# PCB_eagle_project.net
KiCad netlist of a schematic drawn in EAGLE
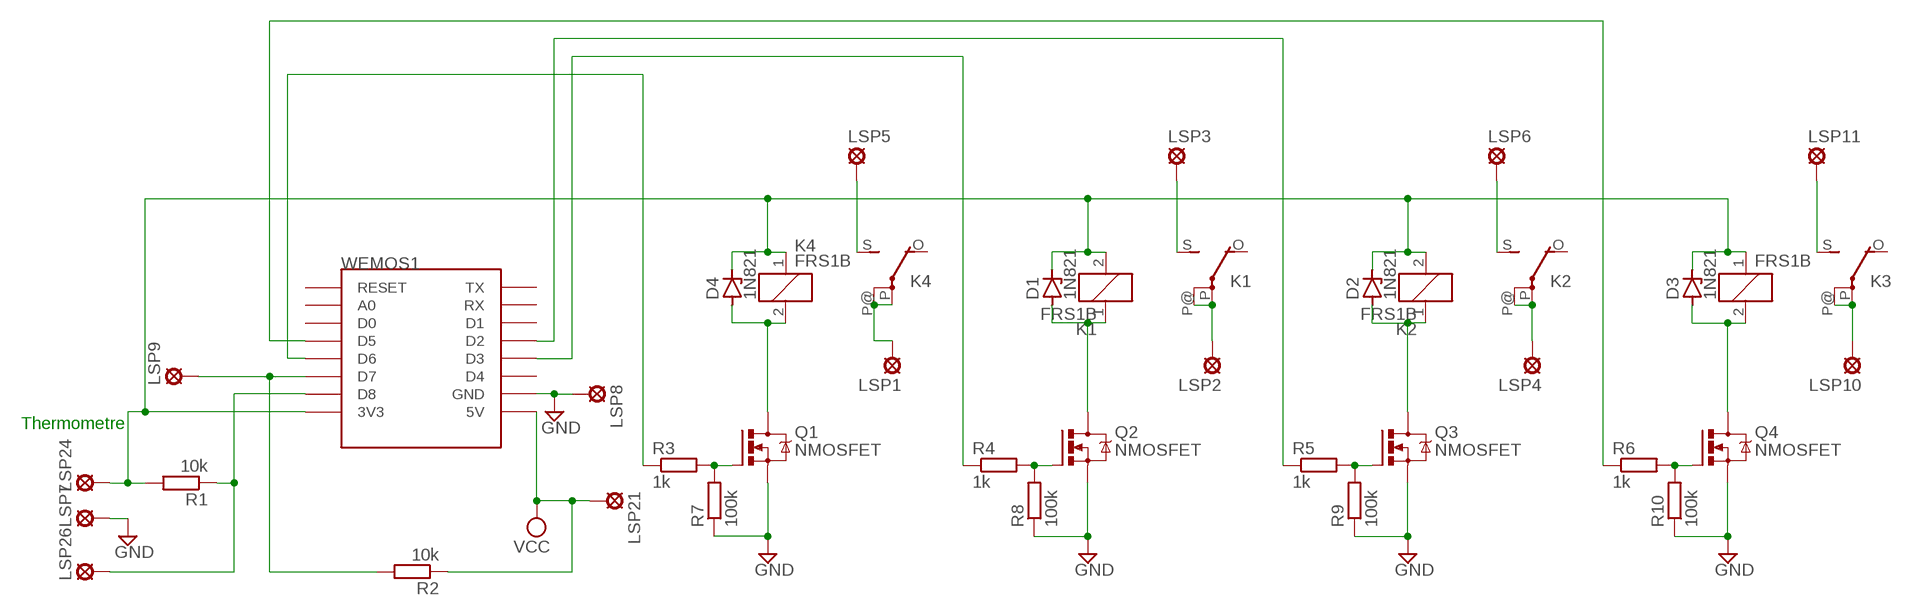
[diagram p0: schematic, sheet 1]

(export (version "E")
  (design (tool "Eeschema 10.0.6"))
  (components
    (comp (ref "D1")
      (value "1N821")
      (footprint "eagle-import:DO35Z10")
      (libsource (lib "eagle-import") (part "1N821"))
    )
    (comp (ref "D2")
      (value "1N821")
      (footprint "eagle-import:DO35Z10")
      (libsource (lib "eagle-import") (part "1N821"))
    )
    (comp (ref "D3")
      (value "1N821")
      (footprint "eagle-import:DO35Z10")
      (libsource (lib "eagle-import") (part "1N821"))
    )
    (comp (ref "D4")
      (value "1N821")
      (footprint "eagle-import:DO35Z10")
      (libsource (lib "eagle-import") (part "1N821"))
    )
    (comp (ref "K1")
      (value "FRS1B")
      (footprint "eagle-import:FRS1B")
      (libsource (lib "eagle-import") (part "FRS1B"))
    )
    (comp (ref "K2")
      (value "FRS1B")
      (footprint "eagle-import:FRS1B")
      (libsource (lib "eagle-import") (part "FRS1B"))
    )
    (comp (ref "K3")
      (value "FRS1B")
      (footprint "eagle-import:FRS1B")
      (libsource (lib "eagle-import") (part "FRS1B"))
    )
    (comp (ref "K4")
      (value "FRS1B")
      (footprint "eagle-import:FRS1B")
      (libsource (lib "eagle-import") (part "FRS1B"))
    )
    (comp (ref "LSP1")
      (value "MCS10B")
      (footprint "eagle-import:MCS10B")
      (libsource (lib "eagle-import") (part "MCS10B"))
    )
    (comp (ref "LSP2")
      (value "MCS10B")
      (footprint "eagle-import:MCS10B")
      (libsource (lib "eagle-import") (part "MCS10B"))
    )
    (comp (ref "LSP3")
      (value "MCS10B")
      (footprint "eagle-import:MCS10B")
      (libsource (lib "eagle-import") (part "MCS10B"))
    )
    (comp (ref "LSP4")
      (value "MCS10B")
      (footprint "eagle-import:MCS10B")
      (libsource (lib "eagle-import") (part "MCS10B"))
    )
    (comp (ref "LSP5")
      (value "MCS10B")
      (footprint "eagle-import:MCS10B")
      (libsource (lib "eagle-import") (part "MCS10B"))
    )
    (comp (ref "LSP6")
      (value "MCS10B")
      (footprint "eagle-import:MCS10B")
      (libsource (lib "eagle-import") (part "MCS10B"))
    )
    (comp (ref "LSP7")
      (value "MCS10B")
      (footprint "eagle-import:MCS10B")
      (libsource (lib "eagle-import") (part "MCS10B"))
    )
    (comp (ref "LSP8")
      (value "MCS10B")
      (footprint "eagle-import:MCS10B")
      (libsource (lib "eagle-import") (part "MCS10B"))
    )
    (comp (ref "LSP9")
      (value "MCS10B")
      (footprint "eagle-import:MCS10B")
      (libsource (lib "eagle-import") (part "MCS10B"))
    )
    (comp (ref "LSP10")
      (value "MCS10B")
      (footprint "eagle-import:MCS10B")
      (libsource (lib "eagle-import") (part "MCS10B"))
    )
    (comp (ref "LSP11")
      (value "MCS10B")
      (footprint "eagle-import:MCS10B")
      (libsource (lib "eagle-import") (part "MCS10B"))
    )
    (comp (ref "LSP21")
      (value "MCS10B")
      (footprint "eagle-import:MCS10B")
      (libsource (lib "eagle-import") (part "MCS10B"))
    )
    (comp (ref "LSP24")
      (value "MCS10B")
      (footprint "eagle-import:MCS10B")
      (libsource (lib "eagle-import") (part "MCS10B"))
    )
    (comp (ref "LSP26")
      (value "MCS10B")
      (footprint "eagle-import:MCS10B")
      (libsource (lib "eagle-import") (part "MCS10B"))
    )
    (comp (ref "Q1")
      (value "NMOSFET")
      (footprint "eagle-import:SOT23")
      (libsource (lib "eagle-import") (part "NMOSFETSOT23-GSD"))
    )
    (comp (ref "Q2")
      (value "NMOSFET")
      (footprint "eagle-import:SOT23")
      (libsource (lib "eagle-import") (part "NMOSFETSOT23-GSD"))
    )
    (comp (ref "Q3")
      (value "NMOSFET")
      (footprint "eagle-import:SOT23")
      (libsource (lib "eagle-import") (part "NMOSFETSOT23-GSD"))
    )
    (comp (ref "Q4")
      (value "NMOSFET")
      (footprint "eagle-import:SOT23")
      (libsource (lib "eagle-import") (part "NMOSFETSOT23-GSD"))
    )
    (comp (ref "R1")
      (value "10k")
      (footprint "eagle-import:0207_10")
      (libsource (lib "eagle-import") (part "R-EU_0207/10"))
    )
    (comp (ref "R2")
      (value "10k")
      (footprint "eagle-import:0207_10")
      (libsource (lib "eagle-import") (part "R-EU_0207/10"))
    )
    (comp (ref "R3")
      (value "1k")
      (footprint "eagle-import:0207_10")
      (libsource (lib "eagle-import") (part "R-EU_0207/10"))
    )
    (comp (ref "R4")
      (value "1k")
      (footprint "eagle-import:0207_10")
      (libsource (lib "eagle-import") (part "R-EU_0207/10"))
    )
    (comp (ref "R5")
      (value "1k")
      (footprint "eagle-import:0207_10")
      (libsource (lib "eagle-import") (part "R-EU_0207/10"))
    )
    (comp (ref "R6")
      (value "1k")
      (footprint "eagle-import:0207_10")
      (libsource (lib "eagle-import") (part "R-EU_0207/10"))
    )
    (comp (ref "R7")
      (value "100k")
      (footprint "eagle-import:0207_10")
      (libsource (lib "eagle-import") (part "R-EU_0207/10"))
    )
    (comp (ref "R8")
      (value "100k")
      (footprint "eagle-import:0207_10")
      (libsource (lib "eagle-import") (part "R-EU_0207/10"))
    )
    (comp (ref "R9")
      (value "100k")
      (footprint "eagle-import:0207_10")
      (libsource (lib "eagle-import") (part "R-EU_0207/10"))
    )
    (comp (ref "R10")
      (value "100k")
      (footprint "eagle-import:0207_10")
      (libsource (lib "eagle-import") (part "R-EU_0207/10"))
    )
    (comp (ref "WEMOS1")
      (value "ui")
      (footprint "eagle-import:WEMOS-D1-MINI")
      (libsource (lib "eagle-import") (part "WEMOS-D1-MINI"))
    )
  )
  (nets
    (net (code "1") (name "GND") (class "Default")
      (node (ref "LSP7") (pin "MP") (pinfunction "MP_MP") (pintype "passive"))
      (node (ref "LSP8") (pin "MP") (pinfunction "MP_MP") (pintype "passive"))
      (node (ref "Q1") (pin "2") (pinfunction "S_2") (pintype "passive"))
      (node (ref "Q2") (pin "2") (pinfunction "S_2") (pintype "passive"))
      (node (ref "Q3") (pin "2") (pinfunction "S_2") (pintype "passive"))
      (node (ref "Q4") (pin "2") (pinfunction "S_2") (pintype "passive"))
      (node (ref "R10") (pin "1") (pinfunction "1_1") (pintype "passive"))
      (node (ref "R7") (pin "1") (pinfunction "1_1") (pintype "passive"))
      (node (ref "R8") (pin "1") (pinfunction "1_1") (pintype "passive"))
      (node (ref "R9") (pin "1") (pinfunction "1_1") (pintype "passive"))
      (node (ref "WEMOS1") (pin "GND") (pinfunction "GND_GND") (pintype "bidirectional"))
    )
    (net (code "2") (name "Net-(D1-PadC)") (class "Default")
      (node (ref "D1") (pin "C") (pinfunction "C_C") (pintype "passive"))
      (node (ref "D2") (pin "C") (pinfunction "C_C") (pintype "passive"))
      (node (ref "D3") (pin "C") (pinfunction "C_C") (pintype "passive"))
      (node (ref "D4") (pin "C") (pinfunction "C_C") (pintype "passive"))
      (node (ref "K1") (pin "2") (pinfunction "2_2") (pintype "passive"))
      (node (ref "K2") (pin "2") (pinfunction "2_2") (pintype "passive"))
      (node (ref "K3") (pin "1") (pinfunction "1_1") (pintype "passive"))
      (node (ref "K4") (pin "1") (pinfunction "1_1") (pintype "passive"))
      (node (ref "LSP24") (pin "MP") (pinfunction "MP_MP") (pintype "passive"))
      (node (ref "R1") (pin "2") (pinfunction "2_2") (pintype "passive"))
      (node (ref "WEMOS1") (pin "3V3") (pinfunction "3V3_3V3") (pintype "bidirectional"))
    )
    (net (code "3") (name "Net-(K1-PadP)") (class "Default")
      (node (ref "K1") (pin "P") (pinfunction "P_P") (pintype "passive"))
      (node (ref "K1") (pin "P@") (pinfunction "P_P@") (pintype "passive"))
      (node (ref "LSP2") (pin "MP") (pinfunction "MP_MP") (pintype "passive"))
    )
    (net (code "4") (name "Net-(K1-PadS)") (class "Default")
      (node (ref "K1") (pin "S") (pinfunction "S_S") (pintype "passive"))
      (node (ref "LSP3") (pin "MP") (pinfunction "MP_MP") (pintype "passive"))
    )
    (net (code "5") (name "Net-(K2-PadP)") (class "Default")
      (node (ref "K2") (pin "P") (pinfunction "P_P") (pintype "passive"))
      (node (ref "K2") (pin "P@") (pinfunction "P_P@") (pintype "passive"))
      (node (ref "LSP4") (pin "MP") (pinfunction "MP_MP") (pintype "passive"))
    )
    (net (code "6") (name "Net-(K2-PadS)") (class "Default")
      (node (ref "K2") (pin "S") (pinfunction "S_S") (pintype "passive"))
      (node (ref "LSP6") (pin "MP") (pinfunction "MP_MP") (pintype "passive"))
    )
    (net (code "7") (name "Net-(K3-PadP)") (class "Default")
      (node (ref "K3") (pin "P") (pinfunction "P_P") (pintype "passive"))
      (node (ref "K3") (pin "P@") (pinfunction "P_P@") (pintype "passive"))
      (node (ref "LSP10") (pin "MP") (pinfunction "MP_MP") (pintype "passive"))
    )
    (net (code "8") (name "Net-(K3-PadS)") (class "Default")
      (node (ref "K3") (pin "S") (pinfunction "S_S") (pintype "passive"))
      (node (ref "LSP11") (pin "MP") (pinfunction "MP_MP") (pintype "passive"))
    )
    (net (code "9") (name "Net-(K4-PadP)") (class "Default")
      (node (ref "K4") (pin "P") (pinfunction "P_P") (pintype "passive"))
      (node (ref "K4") (pin "P@") (pinfunction "P_P@") (pintype "passive"))
      (node (ref "LSP1") (pin "MP") (pinfunction "MP_MP") (pintype "passive"))
    )
    (net (code "10") (name "Net-(K4-PadS)") (class "Default")
      (node (ref "K4") (pin "S") (pinfunction "S_S") (pintype "passive"))
      (node (ref "LSP5") (pin "MP") (pinfunction "MP_MP") (pintype "passive"))
    )
    (net (code "11") (name "Net-(LSP9-PadMP)") (class "Default")
      (node (ref "LSP9") (pin "MP") (pinfunction "MP_MP") (pintype "passive"))
      (node (ref "R2") (pin "2") (pinfunction "2_2") (pintype "passive"))
      (node (ref "WEMOS1") (pin "D7") (pinfunction "D7_D7") (pintype "bidirectional"))
    )
    (net (code "12") (name "Net-(LSP26-PadMP)") (class "Default")
      (node (ref "LSP26") (pin "MP") (pinfunction "MP_MP") (pintype "passive"))
      (node (ref "R1") (pin "1") (pinfunction "1_1") (pintype "passive"))
      (node (ref "WEMOS1") (pin "D8") (pinfunction "D8_D8") (pintype "bidirectional"))
    )
    (net (code "13") (name "Net-(Q1-D)") (class "Default")
      (node (ref "D4") (pin "A") (pinfunction "A_A") (pintype "passive"))
      (node (ref "K4") (pin "2") (pinfunction "2_2") (pintype "passive"))
      (node (ref "Q1") (pin "3") (pinfunction "D_3") (pintype "passive"))
    )
    (net (code "14") (name "Net-(Q1-G)") (class "Default")
      (node (ref "Q1") (pin "1") (pinfunction "G_1") (pintype "passive"))
      (node (ref "R3") (pin "2") (pinfunction "2_2") (pintype "passive"))
      (node (ref "R7") (pin "2") (pinfunction "2_2") (pintype "passive"))
    )
    (net (code "15") (name "Net-(Q2-D)") (class "Default")
      (node (ref "D1") (pin "A") (pinfunction "A_A") (pintype "passive"))
      (node (ref "K1") (pin "1") (pinfunction "1_1") (pintype "passive"))
      (node (ref "Q2") (pin "3") (pinfunction "D_3") (pintype "passive"))
    )
    (net (code "16") (name "Net-(Q2-G)") (class "Default")
      (node (ref "Q2") (pin "1") (pinfunction "G_1") (pintype "passive"))
      (node (ref "R4") (pin "2") (pinfunction "2_2") (pintype "passive"))
      (node (ref "R8") (pin "2") (pinfunction "2_2") (pintype "passive"))
    )
    (net (code "17") (name "Net-(Q3-D)") (class "Default")
      (node (ref "D2") (pin "A") (pinfunction "A_A") (pintype "passive"))
      (node (ref "K2") (pin "1") (pinfunction "1_1") (pintype "passive"))
      (node (ref "Q3") (pin "3") (pinfunction "D_3") (pintype "passive"))
    )
    (net (code "18") (name "Net-(Q3-G)") (class "Default")
      (node (ref "Q3") (pin "1") (pinfunction "G_1") (pintype "passive"))
      (node (ref "R5") (pin "2") (pinfunction "2_2") (pintype "passive"))
      (node (ref "R9") (pin "2") (pinfunction "2_2") (pintype "passive"))
    )
    (net (code "19") (name "Net-(Q4-D)") (class "Default")
      (node (ref "D3") (pin "A") (pinfunction "A_A") (pintype "passive"))
      (node (ref "K3") (pin "2") (pinfunction "2_2") (pintype "passive"))
      (node (ref "Q4") (pin "3") (pinfunction "D_3") (pintype "passive"))
    )
    (net (code "20") (name "Net-(Q4-G)") (class "Default")
      (node (ref "Q4") (pin "1") (pinfunction "G_1") (pintype "passive"))
      (node (ref "R10") (pin "2") (pinfunction "2_2") (pintype "passive"))
      (node (ref "R6") (pin "2") (pinfunction "2_2") (pintype "passive"))
    )
    (net (code "21") (name "Net-(R3-Pad1)") (class "Default")
      (node (ref "R3") (pin "1") (pinfunction "1_1") (pintype "passive"))
      (node (ref "WEMOS1") (pin "D6") (pinfunction "D6_D6") (pintype "bidirectional"))
    )
    (net (code "22") (name "Net-(R4-Pad1)") (class "Default")
      (node (ref "R4") (pin "1") (pinfunction "1_1") (pintype "passive"))
      (node (ref "WEMOS1") (pin "D3") (pinfunction "D3_D3") (pintype "bidirectional"))
    )
    (net (code "23") (name "Net-(R5-Pad1)") (class "Default")
      (node (ref "R5") (pin "1") (pinfunction "1_1") (pintype "passive"))
      (node (ref "WEMOS1") (pin "D2") (pinfunction "D2_D2") (pintype "bidirectional"))
    )
    (net (code "24") (name "Net-(R6-Pad1)") (class "Default")
      (node (ref "R6") (pin "1") (pinfunction "1_1") (pintype "passive"))
      (node (ref "WEMOS1") (pin "D5") (pinfunction "D5_D5") (pintype "bidirectional"))
    )
    (net (code "25") (name "VCC") (class "Default")
      (node (ref "LSP21") (pin "MP") (pinfunction "MP_MP") (pintype "passive"))
      (node (ref "R2") (pin "1") (pinfunction "1_1") (pintype "passive"))
      (node (ref "WEMOS1") (pin "5V") (pinfunction "5V_5V") (pintype "bidirectional"))
    )
    (net (code "26") (name "unconnected-(K1-PadO)") (class "Default")
      (node (ref "K1") (pin "O") (pinfunction "O_O") (pintype "passive"))
    )
    (net (code "27") (name "unconnected-(K2-PadO)") (class "Default")
      (node (ref "K2") (pin "O") (pinfunction "O_O") (pintype "passive"))
    )
    (net (code "28") (name "unconnected-(K3-PadO)") (class "Default")
      (node (ref "K3") (pin "O") (pinfunction "O_O") (pintype "passive"))
    )
    (net (code "29") (name "unconnected-(K4-PadO)") (class "Default")
      (node (ref "K4") (pin "O") (pinfunction "O_O") (pintype "passive"))
    )
    (net (code "30") (name "unconnected-(WEMOS1-PadA0)") (class "Default")
      (node (ref "WEMOS1") (pin "A0") (pinfunction "A0_A0") (pintype "bidirectional"))
    )
    (net (code "31") (name "unconnected-(WEMOS1-PadD0)") (class "Default")
      (node (ref "WEMOS1") (pin "D0") (pinfunction "D0_D0") (pintype "bidirectional"))
    )
    (net (code "32") (name "unconnected-(WEMOS1-PadD1)") (class "Default")
      (node (ref "WEMOS1") (pin "D1") (pinfunction "D1_D1") (pintype "bidirectional"))
    )
    (net (code "33") (name "unconnected-(WEMOS1-PadD4)") (class "Default")
      (node (ref "WEMOS1") (pin "D4") (pinfunction "D4_D4") (pintype "bidirectional"))
    )
    (net (code "34") (name "unconnected-(WEMOS1-PadRESET)") (class "Default")
      (node (ref "WEMOS1") (pin "RESET") (pinfunction "RESET_RESET") (pintype "bidirectional"))
    )
    (net (code "35") (name "unconnected-(WEMOS1-PadRX)") (class "Default")
      (node (ref "WEMOS1") (pin "RX") (pinfunction "RX_RX") (pintype "bidirectional"))
    )
    (net (code "36") (name "unconnected-(WEMOS1-PadTX)") (class "Default")
      (node (ref "WEMOS1") (pin "TX") (pinfunction "TX_TX") (pintype "bidirectional"))
    )
  )
)
